# DCCInterface.net
KiCad netlist of a schematic drawn in EAGLE
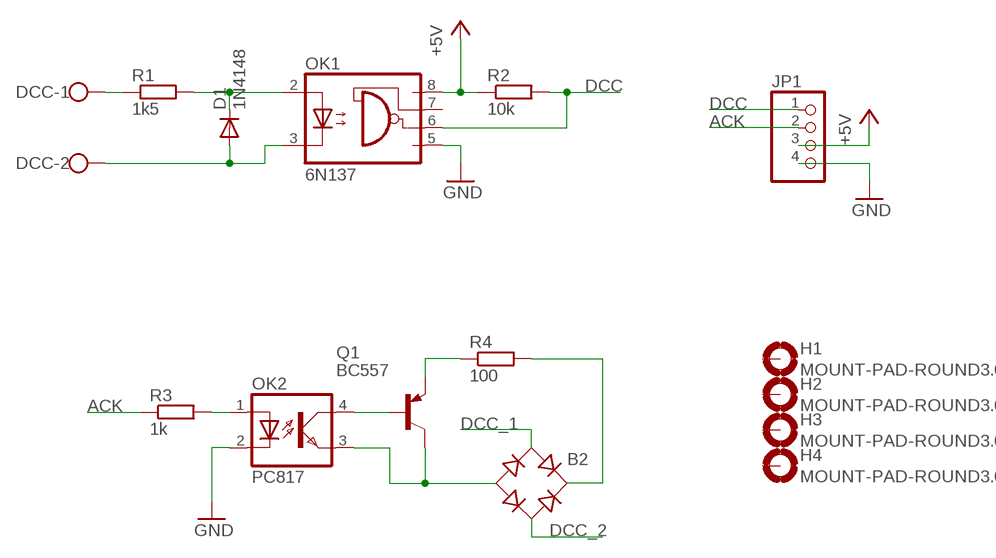
[diagram p0: schematic, sheet 1]

(export (version "E")
  (design (tool "Eeschema 10.0.6"))
  (components
    (comp (ref "B2")
      (value "RB1A")
      (footprint "eagle-import:RB1A")
      (libsource (lib "eagle-import") (part "RB1A"))
    )
    (comp (ref "D1")
      (value "1N4148")
      (footprint "eagle-import:DO35-10")
      (libsource (lib "eagle-import") (part "1N4148DO35-10"))
    )
    (comp (ref "DCC")
      (value "W237-102")
      (footprint "eagle-import:W237-102")
      (fields (field (name "MPN") "237-102"))
      (libsource (lib "eagle-import") (part "W237-102"))
    )
    (comp (ref "H1")
      (value "MOUNT-PAD-ROUND3.0")
      (footprint "eagle-import:3,0-PAD")
      (libsource (lib "eagle-import") (part "MOUNT-PAD-ROUND3.0"))
    )
    (comp (ref "H2")
      (value "MOUNT-PAD-ROUND3.0")
      (footprint "eagle-import:3,0-PAD")
      (libsource (lib "eagle-import") (part "MOUNT-PAD-ROUND3.0"))
    )
    (comp (ref "H3")
      (value "MOUNT-PAD-ROUND3.0")
      (footprint "eagle-import:3,0-PAD")
      (libsource (lib "eagle-import") (part "MOUNT-PAD-ROUND3.0"))
    )
    (comp (ref "H4")
      (value "MOUNT-PAD-ROUND3.0")
      (footprint "eagle-import:3,0-PAD")
      (libsource (lib "eagle-import") (part "MOUNT-PAD-ROUND3.0"))
    )
    (comp (ref "JP1")
      (value "PINHD-1X4")
      (footprint "eagle-import:1X04")
      (libsource (lib "eagle-import") (part "PINHD-1X4"))
    )
    (comp (ref "OK1")
      (value "6N137")
      (footprint "eagle-import:DIL08")
      (libsource (lib "eagle-import") (part "6N137"))
    )
    (comp (ref "OK2")
      (value "PC817")
      (footprint "eagle-import:DIL04")
      (fields (field (name "MPN") "PC817X4J000F"))
      (libsource (lib "eagle-import") (part "PC817"))
    )
    (comp (ref "Q1")
      (value "BC557")
      (footprint "eagle-import:TO92")
      (libsource (lib "eagle-import") (part "BC557"))
    )
    (comp (ref "R1")
      (value "1k5")
      (footprint "eagle-import:0207_10")
      (libsource (lib "eagle-import") (part "R-EU_0207/10"))
    )
    (comp (ref "R2")
      (value "10k")
      (footprint "eagle-import:0207_10")
      (libsource (lib "eagle-import") (part "R-EU_0207/10"))
    )
    (comp (ref "R3")
      (value "1k")
      (footprint "eagle-import:0207_10")
      (libsource (lib "eagle-import") (part "R-EU_0207/10"))
    )
    (comp (ref "R4")
      (value "100")
      (footprint "eagle-import:0207_10")
      (libsource (lib "eagle-import") (part "R-EU_0207/10"))
    )
  )
  (nets
    (net (code "1") (name "+5V") (class "Default")
      (node (ref "JP1") (pin "3") (pinfunction "3_3") (pintype "passive"))
      (node (ref "OK1") (pin "8") (pinfunction "VCC_8") (pintype "passive"))
      (node (ref "R2") (pin "1") (pinfunction "1_1") (pintype "passive"))
    )
    (net (code "2") (name "/ACK") (class "Default")
      (node (ref "JP1") (pin "2") (pinfunction "2_2") (pintype "passive"))
      (node (ref "R3") (pin "1") (pinfunction "1_1") (pintype "passive"))
    )
    (net (code "3") (name "/DCC") (class "Default")
      (node (ref "JP1") (pin "1") (pinfunction "1_1") (pintype "passive"))
      (node (ref "OK1") (pin "6") (pinfunction "VO_6") (pintype "passive"))
      (node (ref "R2") (pin "2") (pinfunction "2_2") (pintype "passive"))
    )
    (net (code "4") (name "/DCC_1") (class "Default")
      (node (ref "B2") (pin "AC1") (pinfunction "AC1_AC1") (pintype "passive"))
      (node (ref "DCC") (pin "1") (pinfunction "KL_1") (pintype "passive"))
      (node (ref "R1") (pin "1") (pinfunction "1_1") (pintype "passive"))
    )
    (net (code "5") (name "/DCC_2") (class "Default")
      (node (ref "B2") (pin "AC2") (pinfunction "AC2_AC2") (pintype "passive"))
      (node (ref "D1") (pin "A") (pinfunction "A_A") (pintype "passive"))
      (node (ref "DCC") (pin "2") (pinfunction "KL_2") (pintype "passive"))
      (node (ref "OK1") (pin "3") (pinfunction "C_3") (pintype "passive"))
    )
    (net (code "6") (name "GND") (class "Default")
      (node (ref "JP1") (pin "4") (pinfunction "4_4") (pintype "passive"))
      (node (ref "OK1") (pin "5") (pinfunction "GND_5") (pintype "passive"))
      (node (ref "OK2") (pin "2") (pinfunction "C_2") (pintype "passive"))
    )
    (net (code "7") (name "Net-(B2-Pad+)") (class "Default")
      (node (ref "B2") (pin "+") (pinfunction "+_+") (pintype "passive"))
      (node (ref "R4") (pin "2") (pinfunction "2_2") (pintype "passive"))
    )
    (net (code "8") (name "Net-(OK1-A)") (class "Default")
      (node (ref "D1") (pin "C") (pinfunction "C_C") (pintype "passive"))
      (node (ref "OK1") (pin "2") (pinfunction "A_2") (pintype "passive"))
      (node (ref "R1") (pin "2") (pinfunction "2_2") (pintype "passive"))
    )
    (net (code "9") (name "Net-(OK2-A)") (class "Default")
      (node (ref "OK2") (pin "1") (pinfunction "A_1") (pintype "passive"))
      (node (ref "R3") (pin "2") (pinfunction "2_2") (pintype "passive"))
    )
    (net (code "10") (name "Net-(OK2-COL)") (class "Default")
      (node (ref "OK2") (pin "4") (pinfunction "COL_4") (pintype "passive"))
      (node (ref "Q1") (pin "2") (pinfunction "B_2") (pintype "passive"))
    )
    (net (code "11") (name "Net-(OK2-EMIT)") (class "Default")
      (node (ref "B2") (pin "-") (pinfunction "-_-") (pintype "passive"))
      (node (ref "OK2") (pin "3") (pinfunction "EMIT_3") (pintype "passive"))
      (node (ref "Q1") (pin "3") (pinfunction "C_3") (pintype "passive"))
    )
    (net (code "12") (name "Net-(Q1-E)") (class "Default")
      (node (ref "Q1") (pin "1") (pinfunction "E_1") (pintype "passive"))
      (node (ref "R4") (pin "1") (pinfunction "1_1") (pintype "passive"))
    )
    (net (code "13") (name "unconnected-(H1-MOUNT-PadB3,0)") (class "Default")
      (node (ref "H1") (pin "B3,0") (pinfunction "MOUNT_B3,0") (pintype "passive"))
    )
    (net (code "14") (name "unconnected-(H2-MOUNT-PadB3,0)") (class "Default")
      (node (ref "H2") (pin "B3,0") (pinfunction "MOUNT_B3,0") (pintype "passive"))
    )
    (net (code "15") (name "unconnected-(H3-MOUNT-PadB3,0)") (class "Default")
      (node (ref "H3") (pin "B3,0") (pinfunction "MOUNT_B3,0") (pintype "passive"))
    )
    (net (code "16") (name "unconnected-(H4-MOUNT-PadB3,0)") (class "Default")
      (node (ref "H4") (pin "B3,0") (pinfunction "MOUNT_B3,0") (pintype "passive"))
    )
    (net (code "17") (name "unconnected-(OK1-VE-Pad7)") (class "Default")
      (node (ref "OK1") (pin "7") (pinfunction "VE_7") (pintype "passive"))
    )
  )
)
